# FPGA_HPCC_B_BG13-15-16.net
KiCad netlist of a schematic drawn in Altium Designer
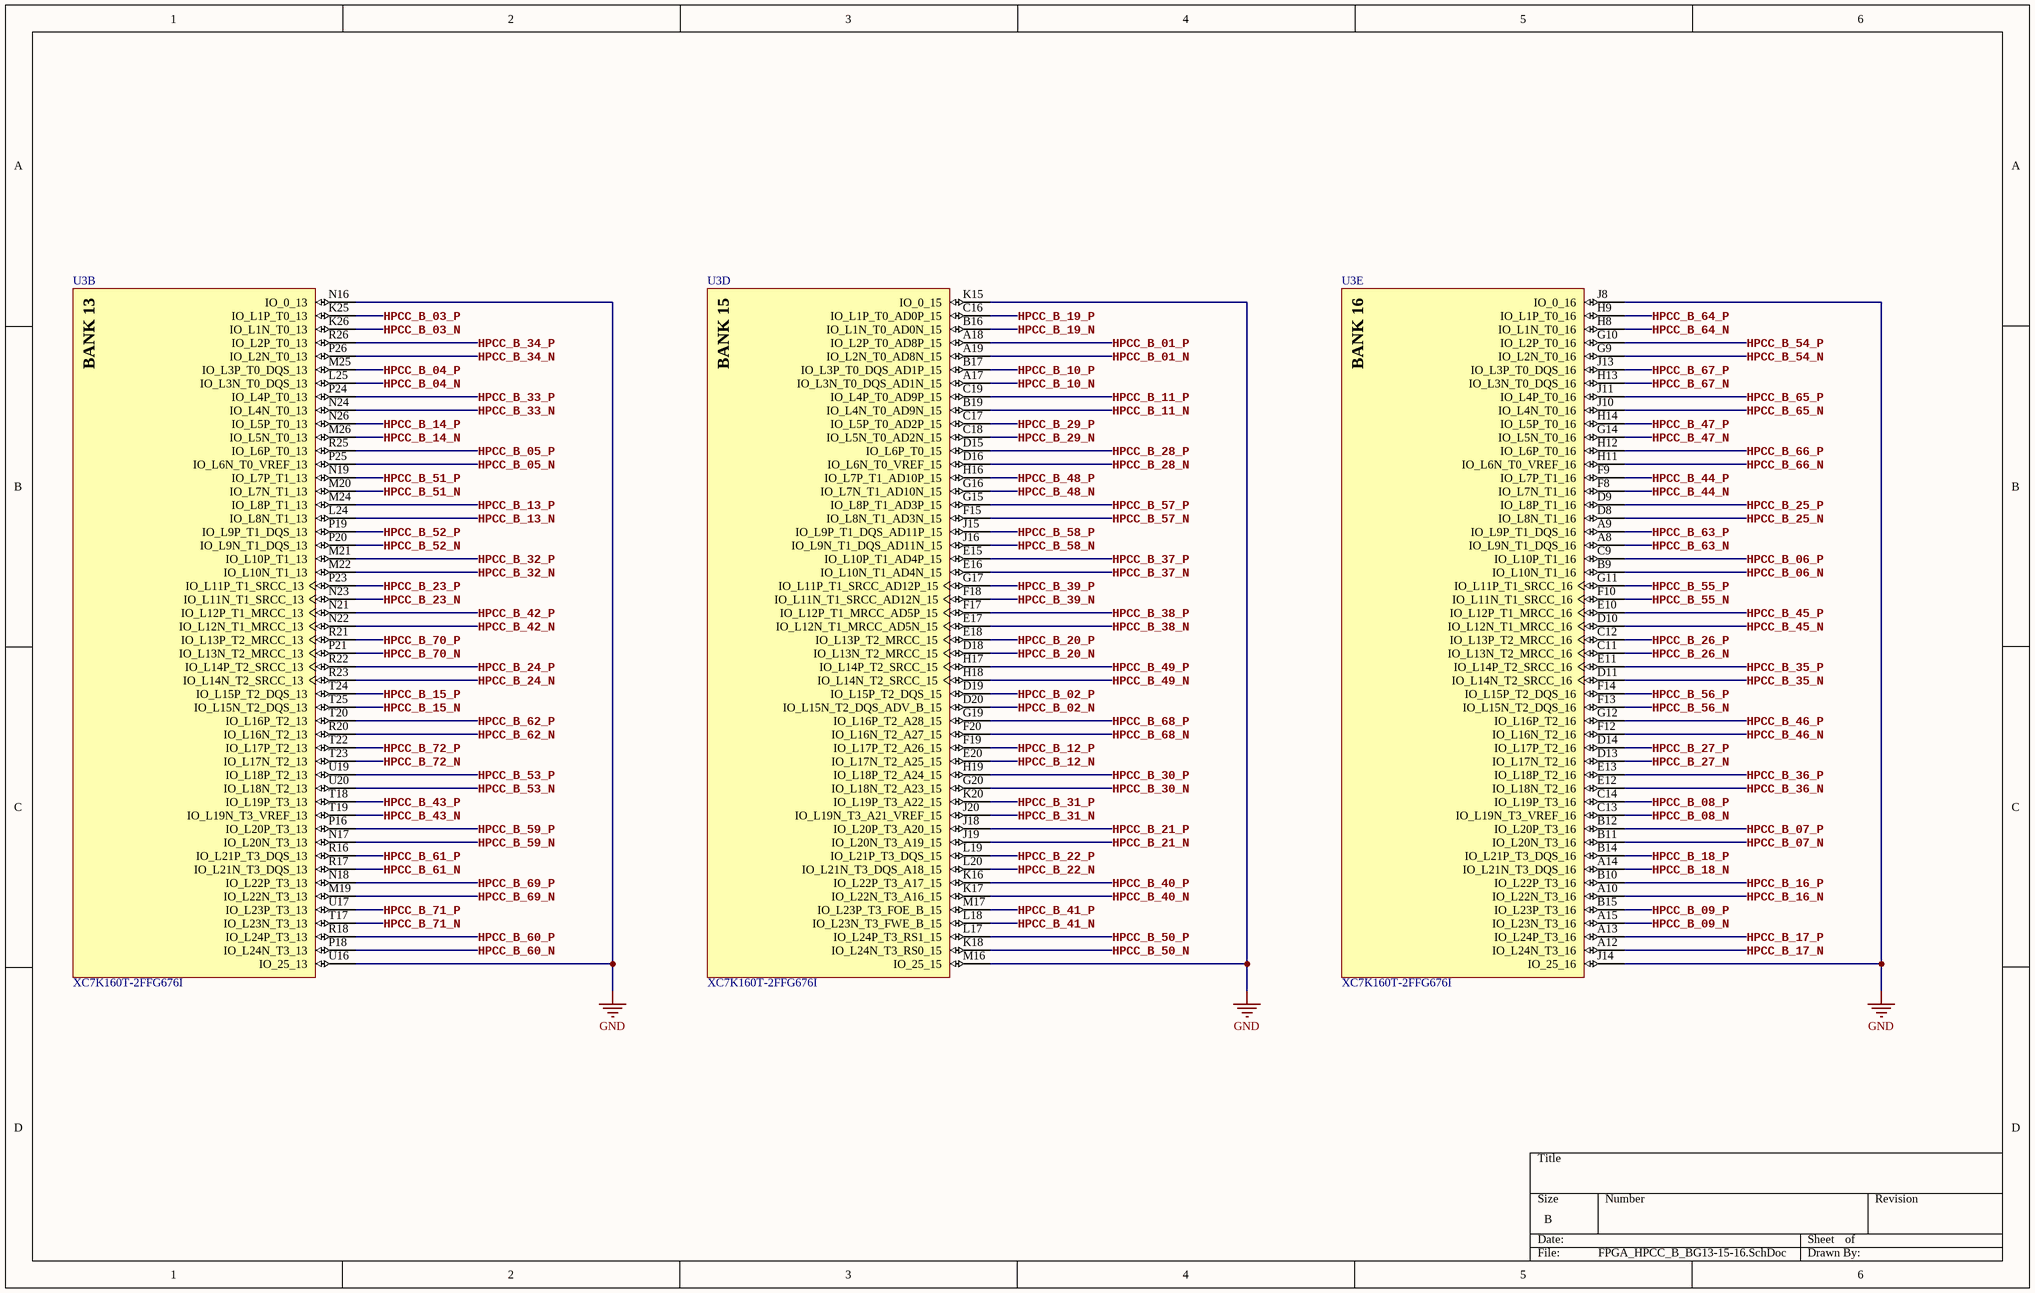
[diagram p0: FPGA_HPCC_B_BG13-15-16.SchDoc]

(export (version "E")
  (design (tool "Eeschema 10.0.6"))
  (components
    (comp (ref "U3")
      (value "XC7K160T-2FFG676I")
      (footprint "FFG676_(XC7K160T-2FFG676I)")
      (description "Kintex-7 FPGA, 400 User I/Os, 8 GTX, 676-Ball BGA, Speed Grade 2, Industrial Grade, Pb-Free")
      (fields (field (name "MANUFACTURER") "AMD/Xilinx"))
      (libsource (lib "Capstone_Schematic_Library") (part "XC7K160T"))
    )
  )
  (nets
    (net (code "1") (name "/HPCC_B_01_N") (class "Default")
      (node (ref "U3") (pin "A19") (pinfunction "IO_L2N_T0_AD8N_15_A19") (pintype "bidirectional"))
    )
    (net (code "2") (name "/HPCC_B_01_P") (class "Default")
      (node (ref "U3") (pin "A18") (pinfunction "IO_L2P_T0_AD8P_15_A18") (pintype "bidirectional"))
    )
    (net (code "3") (name "/HPCC_B_02_N") (class "Default")
      (node (ref "U3") (pin "D20") (pinfunction "IO_L15N_T2_DQS_ADV_B_15_D20") (pintype "bidirectional"))
    )
    (net (code "4") (name "/HPCC_B_02_P") (class "Default")
      (node (ref "U3") (pin "D19") (pinfunction "IO_L15P_T2_DQS_15_D19") (pintype "bidirectional"))
    )
    (net (code "5") (name "/HPCC_B_03_N") (class "Default")
      (node (ref "U3") (pin "K26") (pinfunction "IO_L1N_T0_13_K26") (pintype "bidirectional"))
    )
    (net (code "6") (name "/HPCC_B_03_P") (class "Default")
      (node (ref "U3") (pin "K25") (pinfunction "IO_L1P_T0_13_K25") (pintype "bidirectional"))
    )
    (net (code "7") (name "/HPCC_B_04_N") (class "Default")
      (node (ref "U3") (pin "L25") (pinfunction "IO_L3N_T0_DQS_13_L25") (pintype "bidirectional"))
    )
    (net (code "8") (name "/HPCC_B_04_P") (class "Default")
      (node (ref "U3") (pin "M25") (pinfunction "IO_L3P_T0_DQS_13_M25") (pintype "bidirectional"))
    )
    (net (code "9") (name "/HPCC_B_05_N") (class "Default")
      (node (ref "U3") (pin "P25") (pinfunction "IO_L6N_T0_VREF_13_P25") (pintype "bidirectional"))
    )
    (net (code "10") (name "/HPCC_B_05_P") (class "Default")
      (node (ref "U3") (pin "R25") (pinfunction "IO_L6P_T0_13_R25") (pintype "bidirectional"))
    )
    (net (code "11") (name "/HPCC_B_06_N") (class "Default")
      (node (ref "U3") (pin "B9") (pinfunction "IO_L10N_T1_16_B9") (pintype "bidirectional"))
    )
    (net (code "12") (name "/HPCC_B_06_P") (class "Default")
      (node (ref "U3") (pin "C9") (pinfunction "IO_L10P_T1_16_C9") (pintype "bidirectional"))
    )
    (net (code "13") (name "/HPCC_B_07_N") (class "Default")
      (node (ref "U3") (pin "B11") (pinfunction "IO_L20N_T3_16_B11") (pintype "bidirectional"))
    )
    (net (code "14") (name "/HPCC_B_07_P") (class "Default")
      (node (ref "U3") (pin "B12") (pinfunction "IO_L20P_T3_16_B12") (pintype "bidirectional"))
    )
    (net (code "15") (name "/HPCC_B_08_N") (class "Default")
      (node (ref "U3") (pin "C13") (pinfunction "IO_L19N_T3_VREF_16_C13") (pintype "bidirectional"))
    )
    (net (code "16") (name "/HPCC_B_08_P") (class "Default")
      (node (ref "U3") (pin "C14") (pinfunction "IO_L19P_T3_16_C14") (pintype "bidirectional"))
    )
    (net (code "17") (name "/HPCC_B_09_N") (class "Default")
      (node (ref "U3") (pin "A15") (pinfunction "IO_L23N_T3_16_A15") (pintype "bidirectional"))
    )
    (net (code "18") (name "/HPCC_B_09_P") (class "Default")
      (node (ref "U3") (pin "B15") (pinfunction "IO_L23P_T3_16_B15") (pintype "bidirectional"))
    )
    (net (code "19") (name "/HPCC_B_10_N") (class "Default")
      (node (ref "U3") (pin "A17") (pinfunction "IO_L3N_T0_DQS_AD1N_15_A17") (pintype "bidirectional"))
    )
    (net (code "20") (name "/HPCC_B_10_P") (class "Default")
      (node (ref "U3") (pin "B17") (pinfunction "IO_L3P_T0_DQS_AD1P_15_B17") (pintype "bidirectional"))
    )
    (net (code "21") (name "/HPCC_B_11_N") (class "Default")
      (node (ref "U3") (pin "B19") (pinfunction "IO_L4N_T0_AD9N_15_B19") (pintype "bidirectional"))
    )
    (net (code "22") (name "/HPCC_B_11_P") (class "Default")
      (node (ref "U3") (pin "C19") (pinfunction "IO_L4P_T0_AD9P_15_C19") (pintype "bidirectional"))
    )
    (net (code "23") (name "/HPCC_B_12_N") (class "Default")
      (node (ref "U3") (pin "E20") (pinfunction "IO_L17N_T2_A25_15_E20") (pintype "bidirectional"))
    )
    (net (code "24") (name "/HPCC_B_12_P") (class "Default")
      (node (ref "U3") (pin "F19") (pinfunction "IO_L17P_T2_A26_15_F19") (pintype "bidirectional"))
    )
    (net (code "25") (name "/HPCC_B_13_N") (class "Default")
      (node (ref "U3") (pin "L24") (pinfunction "IO_L8N_T1_13_L24") (pintype "bidirectional"))
    )
    (net (code "26") (name "/HPCC_B_13_P") (class "Default")
      (node (ref "U3") (pin "M24") (pinfunction "IO_L8P_T1_13_M24") (pintype "bidirectional"))
    )
    (net (code "27") (name "/HPCC_B_14_N") (class "Default")
      (node (ref "U3") (pin "M26") (pinfunction "IO_L5N_T0_13_M26") (pintype "bidirectional"))
    )
    (net (code "28") (name "/HPCC_B_14_P") (class "Default")
      (node (ref "U3") (pin "N26") (pinfunction "IO_L5P_T0_13_N26") (pintype "bidirectional"))
    )
    (net (code "29") (name "/HPCC_B_15_N") (class "Default")
      (node (ref "U3") (pin "T25") (pinfunction "IO_L15N_T2_DQS_13_T25") (pintype "bidirectional"))
    )
    (net (code "30") (name "/HPCC_B_15_P") (class "Default")
      (node (ref "U3") (pin "T24") (pinfunction "IO_L15P_T2_DQS_13_T24") (pintype "bidirectional"))
    )
    (net (code "31") (name "/HPCC_B_16_N") (class "Default")
      (node (ref "U3") (pin "A10") (pinfunction "IO_L22N_T3_16_A10") (pintype "bidirectional"))
    )
    (net (code "32") (name "/HPCC_B_16_P") (class "Default")
      (node (ref "U3") (pin "B10") (pinfunction "IO_L22P_T3_16_B10") (pintype "bidirectional"))
    )
    (net (code "33") (name "/HPCC_B_17_N") (class "Default")
      (node (ref "U3") (pin "A12") (pinfunction "IO_L24N_T3_16_A12") (pintype "bidirectional"))
    )
    (net (code "34") (name "/HPCC_B_17_P") (class "Default")
      (node (ref "U3") (pin "A13") (pinfunction "IO_L24P_T3_16_A13") (pintype "bidirectional"))
    )
    (net (code "35") (name "/HPCC_B_18_N") (class "Default")
      (node (ref "U3") (pin "A14") (pinfunction "IO_L21N_T3_DQS_16_A14") (pintype "bidirectional"))
    )
    (net (code "36") (name "/HPCC_B_18_P") (class "Default")
      (node (ref "U3") (pin "B14") (pinfunction "IO_L21P_T3_DQS_16_B14") (pintype "bidirectional"))
    )
    (net (code "37") (name "/HPCC_B_19_N") (class "Default")
      (node (ref "U3") (pin "B16") (pinfunction "IO_L1N_T0_AD0N_15_B16") (pintype "bidirectional"))
    )
    (net (code "38") (name "/HPCC_B_19_P") (class "Default")
      (node (ref "U3") (pin "C16") (pinfunction "IO_L1P_T0_AD0P_15_C16") (pintype "bidirectional"))
    )
    (net (code "39") (name "/HPCC_B_20_N") (class "Default")
      (node (ref "U3") (pin "D18") (pinfunction "IO_L13N_T2_MRCC_15_D18") (pintype "bidirectional"))
    )
    (net (code "40") (name "/HPCC_B_20_P") (class "Default")
      (node (ref "U3") (pin "E18") (pinfunction "IO_L13P_T2_MRCC_15_E18") (pintype "bidirectional"))
    )
    (net (code "41") (name "/HPCC_B_21_N") (class "Default")
      (node (ref "U3") (pin "J19") (pinfunction "IO_L20N_T3_A19_15_J19") (pintype "bidirectional"))
    )
    (net (code "42") (name "/HPCC_B_21_P") (class "Default")
      (node (ref "U3") (pin "J18") (pinfunction "IO_L20P_T3_A20_15_J18") (pintype "bidirectional"))
    )
    (net (code "43") (name "/HPCC_B_22_N") (class "Default")
      (node (ref "U3") (pin "L20") (pinfunction "IO_L21N_T3_DQS_A18_15_L20") (pintype "bidirectional"))
    )
    (net (code "44") (name "/HPCC_B_22_P") (class "Default")
      (node (ref "U3") (pin "L19") (pinfunction "IO_L21P_T3_DQS_15_L19") (pintype "bidirectional"))
    )
    (net (code "45") (name "/HPCC_B_23_N") (class "Default")
      (node (ref "U3") (pin "N23") (pinfunction "IO_L11N_T1_SRCC_13_N23") (pintype "bidirectional"))
    )
    (net (code "46") (name "/HPCC_B_23_P") (class "Default")
      (node (ref "U3") (pin "P23") (pinfunction "IO_L11P_T1_SRCC_13_P23") (pintype "bidirectional"))
    )
    (net (code "47") (name "/HPCC_B_24_N") (class "Default")
      (node (ref "U3") (pin "R23") (pinfunction "IO_L14N_T2_SRCC_13_R23") (pintype "bidirectional"))
    )
    (net (code "48") (name "/HPCC_B_24_P") (class "Default")
      (node (ref "U3") (pin "R22") (pinfunction "IO_L14P_T2_SRCC_13_R22") (pintype "bidirectional"))
    )
    (net (code "49") (name "/HPCC_B_25_N") (class "Default")
      (node (ref "U3") (pin "D8") (pinfunction "IO_L8N_T1_16_D8") (pintype "bidirectional"))
    )
    (net (code "50") (name "/HPCC_B_25_P") (class "Default")
      (node (ref "U3") (pin "D9") (pinfunction "IO_L8P_T1_16_D9") (pintype "bidirectional"))
    )
    (net (code "51") (name "/HPCC_B_26_N") (class "Default")
      (node (ref "U3") (pin "C11") (pinfunction "IO_L13N_T2_MRCC_16_C11") (pintype "bidirectional"))
    )
    (net (code "52") (name "/HPCC_B_26_P") (class "Default")
      (node (ref "U3") (pin "C12") (pinfunction "IO_L13P_T2_MRCC_16_C12") (pintype "bidirectional"))
    )
    (net (code "53") (name "/HPCC_B_27_N") (class "Default")
      (node (ref "U3") (pin "D13") (pinfunction "IO_L17N_T2_16_D13") (pintype "bidirectional"))
    )
    (net (code "54") (name "/HPCC_B_27_P") (class "Default")
      (node (ref "U3") (pin "D14") (pinfunction "IO_L17P_T2_16_D14") (pintype "bidirectional"))
    )
    (net (code "55") (name "/HPCC_B_28_N") (class "Default")
      (node (ref "U3") (pin "D16") (pinfunction "IO_L6N_T0_VREF_15_D16") (pintype "bidirectional"))
    )
    (net (code "56") (name "/HPCC_B_28_P") (class "Default")
      (node (ref "U3") (pin "D15") (pinfunction "IO_L6P_T0_15_D15") (pintype "bidirectional"))
    )
    (net (code "57") (name "/HPCC_B_29_N") (class "Default")
      (node (ref "U3") (pin "C18") (pinfunction "IO_L5N_T0_AD2N_15_C18") (pintype "bidirectional"))
    )
    (net (code "58") (name "/HPCC_B_29_P") (class "Default")
      (node (ref "U3") (pin "C17") (pinfunction "IO_L5P_T0_AD2P_15_C17") (pintype "bidirectional"))
    )
    (net (code "59") (name "/HPCC_B_30_N") (class "Default")
      (node (ref "U3") (pin "G20") (pinfunction "IO_L18N_T2_A23_15_G20") (pintype "bidirectional"))
    )
    (net (code "60") (name "/HPCC_B_30_P") (class "Default")
      (node (ref "U3") (pin "H19") (pinfunction "IO_L18P_T2_A24_15_H19") (pintype "bidirectional"))
    )
    (net (code "61") (name "/HPCC_B_31_N") (class "Default")
      (node (ref "U3") (pin "J20") (pinfunction "IO_L19N_T3_A21_VREF_15_J20") (pintype "bidirectional"))
    )
    (net (code "62") (name "/HPCC_B_31_P") (class "Default")
      (node (ref "U3") (pin "K20") (pinfunction "IO_L19P_T3_A22_15_K20") (pintype "bidirectional"))
    )
    (net (code "63") (name "/HPCC_B_32_N") (class "Default")
      (node (ref "U3") (pin "M22") (pinfunction "IO_L10N_T1_13_M22") (pintype "bidirectional"))
    )
    (net (code "64") (name "/HPCC_B_32_P") (class "Default")
      (node (ref "U3") (pin "M21") (pinfunction "IO_L10P_T1_13_M21") (pintype "bidirectional"))
    )
    (net (code "65") (name "/HPCC_B_33_N") (class "Default")
      (node (ref "U3") (pin "N24") (pinfunction "IO_L4N_T0_13_N24") (pintype "bidirectional"))
    )
    (net (code "66") (name "/HPCC_B_33_P") (class "Default")
      (node (ref "U3") (pin "P24") (pinfunction "IO_L4P_T0_13_P24") (pintype "bidirectional"))
    )
    (net (code "67") (name "/HPCC_B_34_N") (class "Default")
      (node (ref "U3") (pin "P26") (pinfunction "IO_L2N_T0_13_P26") (pintype "bidirectional"))
    )
    (net (code "68") (name "/HPCC_B_34_P") (class "Default")
      (node (ref "U3") (pin "R26") (pinfunction "IO_L2P_T0_13_R26") (pintype "bidirectional"))
    )
    (net (code "69") (name "/HPCC_B_35_N") (class "Default")
      (node (ref "U3") (pin "D11") (pinfunction "IO_L14N_T2_SRCC_16_D11") (pintype "bidirectional"))
    )
    (net (code "70") (name "/HPCC_B_35_P") (class "Default")
      (node (ref "U3") (pin "E11") (pinfunction "IO_L14P_T2_SRCC_16_E11") (pintype "bidirectional"))
    )
    (net (code "71") (name "/HPCC_B_36_N") (class "Default")
      (node (ref "U3") (pin "E12") (pinfunction "IO_L18N_T2_16_E12") (pintype "bidirectional"))
    )
    (net (code "72") (name "/HPCC_B_36_P") (class "Default")
      (node (ref "U3") (pin "E13") (pinfunction "IO_L18P_T2_16_E13") (pintype "bidirectional"))
    )
    (net (code "73") (name "/HPCC_B_37_N") (class "Default")
      (node (ref "U3") (pin "E16") (pinfunction "IO_L10N_T1_AD4N_15_E16") (pintype "bidirectional"))
    )
    (net (code "74") (name "/HPCC_B_37_P") (class "Default")
      (node (ref "U3") (pin "E15") (pinfunction "IO_L10P_T1_AD4P_15_E15") (pintype "bidirectional"))
    )
    (net (code "75") (name "/HPCC_B_38_N") (class "Default")
      (node (ref "U3") (pin "E17") (pinfunction "IO_L12N_T1_MRCC_AD5N_15_E17") (pintype "bidirectional"))
    )
    (net (code "76") (name "/HPCC_B_38_P") (class "Default")
      (node (ref "U3") (pin "F17") (pinfunction "IO_L12P_T1_MRCC_AD5P_15_F17") (pintype "bidirectional"))
    )
    (net (code "77") (name "/HPCC_B_39_N") (class "Default")
      (node (ref "U3") (pin "F18") (pinfunction "IO_L11N_T1_SRCC_AD12N_15_F18") (pintype "bidirectional"))
    )
    (net (code "78") (name "/HPCC_B_39_P") (class "Default")
      (node (ref "U3") (pin "G17") (pinfunction "IO_L11P_T1_SRCC_AD12P_15_G17") (pintype "bidirectional"))
    )
    (net (code "79") (name "/HPCC_B_40_N") (class "Default")
      (node (ref "U3") (pin "K17") (pinfunction "IO_L22N_T3_A16_15_K17") (pintype "bidirectional"))
    )
    (net (code "80") (name "/HPCC_B_40_P") (class "Default")
      (node (ref "U3") (pin "K16") (pinfunction "IO_L22P_T3_A17_15_K16") (pintype "bidirectional"))
    )
    (net (code "81") (name "/HPCC_B_41_N") (class "Default")
      (node (ref "U3") (pin "L18") (pinfunction "IO_L23N_T3_FWE_B_15_L18") (pintype "bidirectional"))
    )
    (net (code "82") (name "/HPCC_B_41_P") (class "Default")
      (node (ref "U3") (pin "M17") (pinfunction "IO_L23P_T3_FOE_B_15_M17") (pintype "bidirectional"))
    )
    (net (code "83") (name "/HPCC_B_42_N") (class "Default")
      (node (ref "U3") (pin "N22") (pinfunction "IO_L12N_T1_MRCC_13_N22") (pintype "bidirectional"))
    )
    (net (code "84") (name "/HPCC_B_42_P") (class "Default")
      (node (ref "U3") (pin "N21") (pinfunction "IO_L12P_T1_MRCC_13_N21") (pintype "bidirectional"))
    )
    (net (code "85") (name "/HPCC_B_43_N") (class "Default")
      (node (ref "U3") (pin "T19") (pinfunction "IO_L19N_T3_VREF_13_T19") (pintype "bidirectional"))
    )
    (net (code "86") (name "/HPCC_B_43_P") (class "Default")
      (node (ref "U3") (pin "T18") (pinfunction "IO_L19P_T3_13_T18") (pintype "bidirectional"))
    )
    (net (code "87") (name "/HPCC_B_44_N") (class "Default")
      (node (ref "U3") (pin "F8") (pinfunction "IO_L7N_T1_16_F8") (pintype "bidirectional"))
    )
    (net (code "88") (name "/HPCC_B_44_P") (class "Default")
      (node (ref "U3") (pin "F9") (pinfunction "IO_L7P_T1_16_F9") (pintype "bidirectional"))
    )
    (net (code "89") (name "/HPCC_B_45_N") (class "Default")
      (node (ref "U3") (pin "D10") (pinfunction "IO_L12N_T1_MRCC_16_D10") (pintype "bidirectional"))
    )
    (net (code "90") (name "/HPCC_B_45_P") (class "Default")
      (node (ref "U3") (pin "E10") (pinfunction "IO_L12P_T1_MRCC_16_E10") (pintype "bidirectional"))
    )
    (net (code "91") (name "/HPCC_B_46_N") (class "Default")
      (node (ref "U3") (pin "F12") (pinfunction "IO_L16N_T2_16_F12") (pintype "bidirectional"))
    )
    (net (code "92") (name "/HPCC_B_46_P") (class "Default")
      (node (ref "U3") (pin "G12") (pinfunction "IO_L16P_T2_16_G12") (pintype "bidirectional"))
    )
    (net (code "93") (name "/HPCC_B_47_N") (class "Default")
      (node (ref "U3") (pin "G14") (pinfunction "IO_L5N_T0_16_G14") (pintype "bidirectional"))
    )
    (net (code "94") (name "/HPCC_B_47_P") (class "Default")
      (node (ref "U3") (pin "H14") (pinfunction "IO_L5P_T0_16_H14") (pintype "bidirectional"))
    )
    (net (code "95") (name "/HPCC_B_48_N") (class "Default")
      (node (ref "U3") (pin "G16") (pinfunction "IO_L7N_T1_AD10N_15_G16") (pintype "bidirectional"))
    )
    (net (code "96") (name "/HPCC_B_48_P") (class "Default")
      (node (ref "U3") (pin "H16") (pinfunction "IO_L7P_T1_AD10P_15_H16") (pintype "bidirectional"))
    )
    (net (code "97") (name "/HPCC_B_49_N") (class "Default")
      (node (ref "U3") (pin "H18") (pinfunction "IO_L14N_T2_SRCC_15_H18") (pintype "bidirectional"))
    )
    (net (code "98") (name "/HPCC_B_49_P") (class "Default")
      (node (ref "U3") (pin "H17") (pinfunction "IO_L14P_T2_SRCC_15_H17") (pintype "bidirectional"))
    )
    (net (code "99") (name "/HPCC_B_50_N") (class "Default")
      (node (ref "U3") (pin "K18") (pinfunction "IO_L24N_T3_RS0_15_K18") (pintype "bidirectional"))
    )
    (net (code "100") (name "/HPCC_B_50_P") (class "Default")
      (node (ref "U3") (pin "L17") (pinfunction "IO_L24P_T3_RS1_15_L17") (pintype "bidirectional"))
    )
    (net (code "101") (name "/HPCC_B_51_N") (class "Default")
      (node (ref "U3") (pin "M20") (pinfunction "IO_L7N_T1_13_M20") (pintype "bidirectional"))
    )
    (net (code "102") (name "/HPCC_B_51_P") (class "Default")
      (node (ref "U3") (pin "N19") (pinfunction "IO_L7P_T1_13_N19") (pintype "bidirectional"))
    )
    (net (code "103") (name "/HPCC_B_52_N") (class "Default")
      (node (ref "U3") (pin "P20") (pinfunction "IO_L9N_T1_DQS_13_P20") (pintype "bidirectional"))
    )
    (net (code "104") (name "/HPCC_B_52_P") (class "Default")
      (node (ref "U3") (pin "P19") (pinfunction "IO_L9P_T1_DQS_13_P19") (pintype "bidirectional"))
    )
    (net (code "105") (name "/HPCC_B_53_N") (class "Default")
      (node (ref "U3") (pin "U20") (pinfunction "IO_L18N_T2_13_U20") (pintype "bidirectional"))
    )
    (net (code "106") (name "/HPCC_B_53_P") (class "Default")
      (node (ref "U3") (pin "U19") (pinfunction "IO_L18P_T2_13_U19") (pintype "bidirectional"))
    )
    (net (code "107") (name "/HPCC_B_54_N") (class "Default")
      (node (ref "U3") (pin "G9") (pinfunction "IO_L2N_T0_16_G9") (pintype "bidirectional"))
    )
    (net (code "108") (name "/HPCC_B_54_P") (class "Default")
      (node (ref "U3") (pin "G10") (pinfunction "IO_L2P_T0_16_G10") (pintype "bidirectional"))
    )
    (net (code "109") (name "/HPCC_B_55_N") (class "Default")
      (node (ref "U3") (pin "F10") (pinfunction "IO_L11N_T1_SRCC_16_F10") (pintype "bidirectional"))
    )
    (net (code "110") (name "/HPCC_B_55_P") (class "Default")
      (node (ref "U3") (pin "G11") (pinfunction "IO_L11P_T1_SRCC_16_G11") (pintype "bidirectional"))
    )
    (net (code "111") (name "/HPCC_B_56_N") (class "Default")
      (node (ref "U3") (pin "F13") (pinfunction "IO_L15N_T2_DQS_16_F13") (pintype "bidirectional"))
    )
    (net (code "112") (name "/HPCC_B_56_P") (class "Default")
      (node (ref "U3") (pin "F14") (pinfunction "IO_L15P_T2_DQS_16_F14") (pintype "bidirectional"))
    )
    (net (code "113") (name "/HPCC_B_57_N") (class "Default")
      (node (ref "U3") (pin "F15") (pinfunction "IO_L8N_T1_AD3N_15_F15") (pintype "bidirectional"))
    )
    (net (code "114") (name "/HPCC_B_57_P") (class "Default")
      (node (ref "U3") (pin "G15") (pinfunction "IO_L8P_T1_AD3P_15_G15") (pintype "bidirectional"))
    )
    (net (code "115") (name "/HPCC_B_58_N") (class "Default")
      (node (ref "U3") (pin "J16") (pinfunction "IO_L9N_T1_DQS_AD11N_15_J16") (pintype "bidirectional"))
    )
    (net (code "116") (name "/HPCC_B_58_P") (class "Default")
      (node (ref "U3") (pin "J15") (pinfunction "IO_L9P_T1_DQS_AD11P_15_J15") (pintype "bidirectional"))
    )
    (net (code "117") (name "/HPCC_B_59_N") (class "Default")
      (node (ref "U3") (pin "N17") (pinfunction "IO_L20N_T3_13_N17") (pintype "bidirectional"))
    )
    (net (code "118") (name "/HPCC_B_59_P") (class "Default")
      (node (ref "U3") (pin "P16") (pinfunction "IO_L20P_T3_13_P16") (pintype "bidirectional"))
    )
    (net (code "119") (name "/HPCC_B_60_N") (class "Default")
      (node (ref "U3") (pin "P18") (pinfunction "IO_L24N_T3_13_P18") (pintype "bidirectional"))
    )
    (net (code "120") (name "/HPCC_B_60_P") (class "Default")
      (node (ref "U3") (pin "R18") (pinfunction "IO_L24P_T3_13_R18") (pintype "bidirectional"))
    )
    (net (code "121") (name "/HPCC_B_61_N") (class "Default")
      (node (ref "U3") (pin "R17") (pinfunction "IO_L21N_T3_DQS_13_R17") (pintype "bidirectional"))
    )
    (net (code "122") (name "/HPCC_B_61_P") (class "Default")
      (node (ref "U3") (pin "R16") (pinfunction "IO_L21P_T3_DQS_13_R16") (pintype "bidirectional"))
    )
    (net (code "123") (name "/HPCC_B_62_N") (class "Default")
      (node (ref "U3") (pin "R20") (pinfunction "IO_L16N_T2_13_R20") (pintype "bidirectional"))
    )
    (net (code "124") (name "/HPCC_B_62_P") (class "Default")
      (node (ref "U3") (pin "T20") (pinfunction "IO_L16P_T2_13_T20") (pintype "bidirectional"))
    )
    (net (code "125") (name "/HPCC_B_63_N") (class "Default")
      (node (ref "U3") (pin "A8") (pinfunction "IO_L9N_T1_DQS_16_A8") (pintype "bidirectional"))
    )
    (net (code "126") (name "/HPCC_B_63_P") (class "Default")
      (node (ref "U3") (pin "A9") (pinfunction "IO_L9P_T1_DQS_16_A9") (pintype "bidirectional"))
    )
    (net (code "127") (name "/HPCC_B_64_N") (class "Default")
      (node (ref "U3") (pin "H8") (pinfunction "IO_L1N_T0_16_H8") (pintype "bidirectional"))
    )
    (net (code "128") (name "/HPCC_B_64_P") (class "Default")
      (node (ref "U3") (pin "H9") (pinfunction "IO_L1P_T0_16_H9") (pintype "bidirectional"))
    )
    (net (code "129") (name "/HPCC_B_65_N") (class "Default")
      (node (ref "U3") (pin "J10") (pinfunction "IO_L4N_T0_16_J10") (pintype "bidirectional"))
    )
    (net (code "130") (name "/HPCC_B_65_P") (class "Default")
      (node (ref "U3") (pin "J11") (pinfunction "IO_L4P_T0_16_J11") (pintype "bidirectional"))
    )
    (net (code "131") (name "/HPCC_B_66_N") (class "Default")
      (node (ref "U3") (pin "H11") (pinfunction "IO_L6N_T0_VREF_16_H11") (pintype "bidirectional"))
    )
    (net (code "132") (name "/HPCC_B_66_P") (class "Default")
      (node (ref "U3") (pin "H12") (pinfunction "IO_L6P_T0_16_H12") (pintype "bidirectional"))
    )
    (net (code "133") (name "/HPCC_B_67_N") (class "Default")
      (node (ref "U3") (pin "H13") (pinfunction "IO_L3N_T0_DQS_16_H13") (pintype "bidirectional"))
    )
    (net (code "134") (name "/HPCC_B_67_P") (class "Default")
      (node (ref "U3") (pin "J13") (pinfunction "IO_L3P_T0_DQS_16_J13") (pintype "bidirectional"))
    )
    (net (code "135") (name "/HPCC_B_68_N") (class "Default")
      (node (ref "U3") (pin "F20") (pinfunction "IO_L16N_T2_A27_15_F20") (pintype "bidirectional"))
    )
    (net (code "136") (name "/HPCC_B_68_P") (class "Default")
      (node (ref "U3") (pin "G19") (pinfunction "IO_L16P_T2_A28_15_G19") (pintype "bidirectional"))
    )
    (net (code "137") (name "/HPCC_B_69_N") (class "Default")
      (node (ref "U3") (pin "M19") (pinfunction "IO_L22N_T3_13_M19") (pintype "bidirectional"))
    )
    (net (code "138") (name "/HPCC_B_69_P") (class "Default")
      (node (ref "U3") (pin "N18") (pinfunction "IO_L22P_T3_13_N18") (pintype "bidirectional"))
    )
    (net (code "139") (name "/HPCC_B_70_N") (class "Default")
      (node (ref "U3") (pin "P21") (pinfunction "IO_L13N_T2_MRCC_13_P21") (pintype "bidirectional"))
    )
    (net (code "140") (name "/HPCC_B_70_P") (class "Default")
      (node (ref "U3") (pin "R21") (pinfunction "IO_L13P_T2_MRCC_13_R21") (pintype "bidirectional"))
    )
    (net (code "141") (name "/HPCC_B_71_N") (class "Default")
      (node (ref "U3") (pin "T17") (pinfunction "IO_L23N_T3_13_T17") (pintype "bidirectional"))
    )
    (net (code "142") (name "/HPCC_B_71_P") (class "Default")
      (node (ref "U3") (pin "U17") (pinfunction "IO_L23P_T3_13_U17") (pintype "bidirectional"))
    )
    (net (code "143") (name "/HPCC_B_72_N") (class "Default")
      (node (ref "U3") (pin "T23") (pinfunction "IO_L17N_T2_13_T23") (pintype "bidirectional"))
    )
    (net (code "144") (name "/HPCC_B_72_P") (class "Default")
      (node (ref "U3") (pin "T22") (pinfunction "IO_L17P_T2_13_T22") (pintype "bidirectional"))
    )
    (net (code "145") (name "GND") (class "Default")
      (node (ref "U3") (pin "J14") (pinfunction "IO_25_16_J14") (pintype "bidirectional"))
      (node (ref "U3") (pin "J8") (pinfunction "IO_0_16_J8") (pintype "bidirectional"))
      (node (ref "U3") (pin "K15") (pinfunction "IO_0_15_K15") (pintype "bidirectional"))
      (node (ref "U3") (pin "M16") (pinfunction "IO_25_15_M16") (pintype "bidirectional"))
      (node (ref "U3") (pin "N16") (pinfunction "IO_0_13_N16") (pintype "bidirectional"))
      (node (ref "U3") (pin "U16") (pinfunction "IO_25_13_U16") (pintype "bidirectional"))
    )
  )
)
